# MCU.net
KiCad netlist of a schematic drawn in Altium Designer
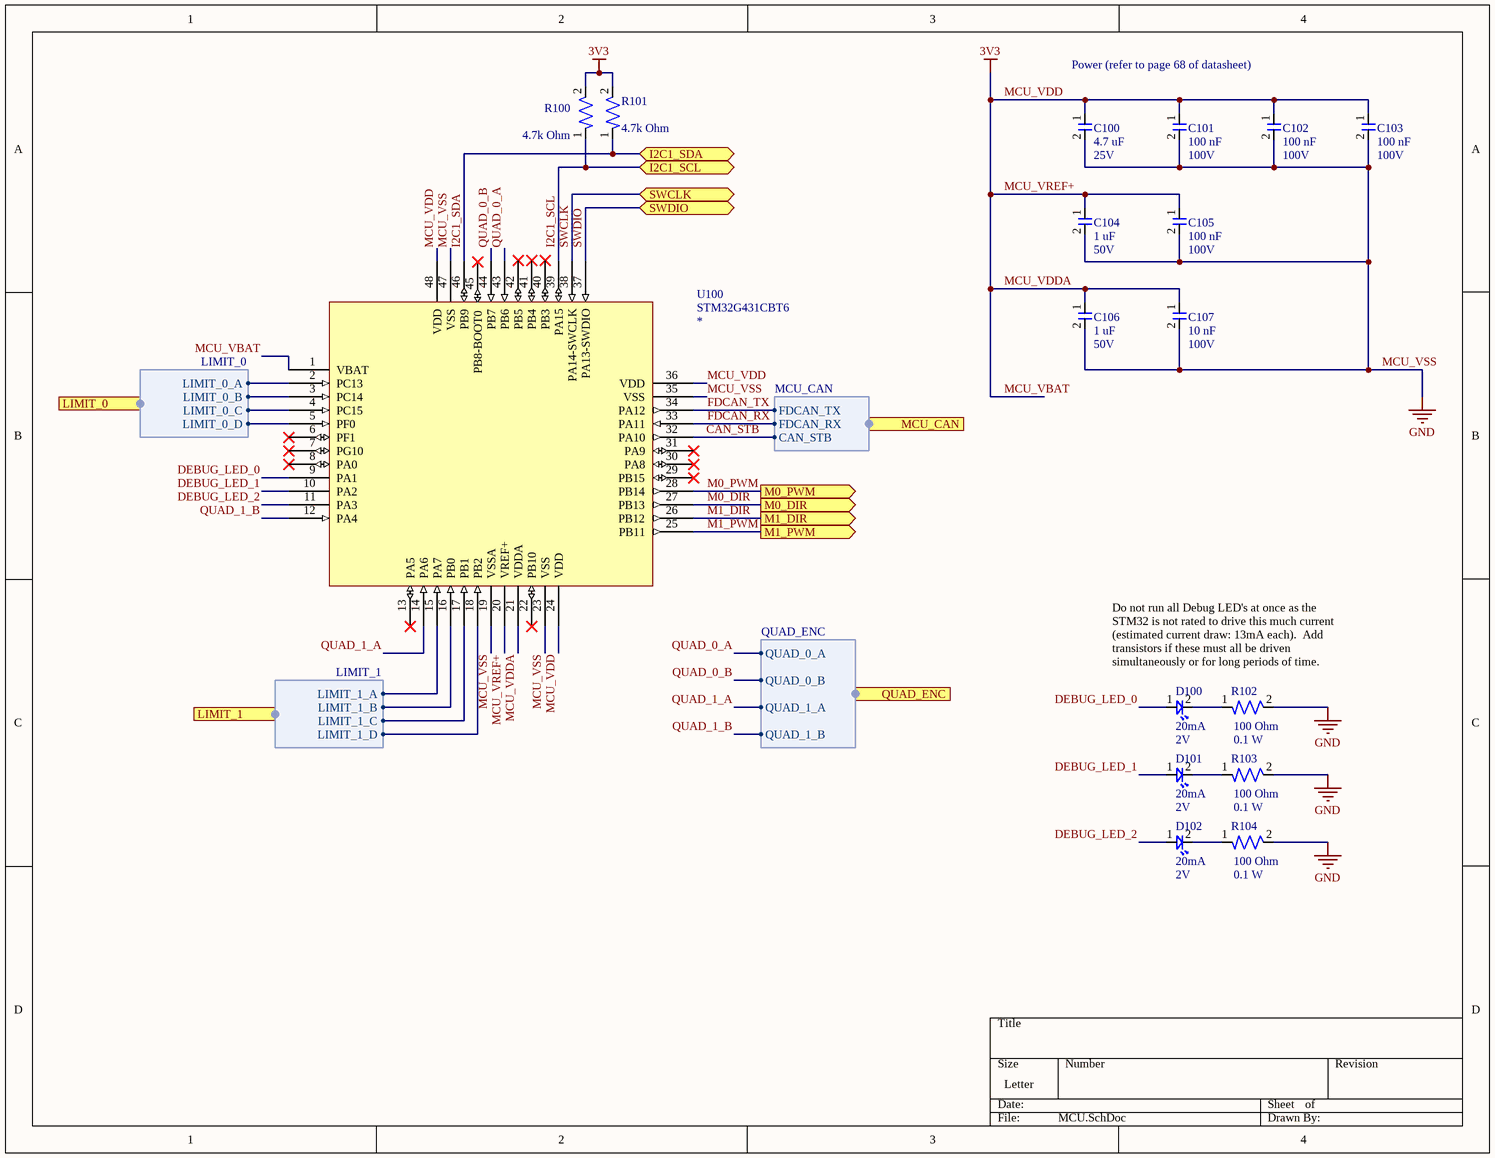
[diagram p0: MCU.SchDoc]

(export (version "E")
  (design (tool "Eeschema 10.0.6"))
  (components
    (comp (ref "C100")
      (value "TMK107BBJ475KA-T")
      (footprint "MasterLib:CAP-0603")
      (description "4.7 µF ±10% 25V Ceramic Capacitor X5R 0603 (1608 Metric)")
      (fields
        (field (name "MANUFACTURER") "Taiyo Yuden")
        (field (name "CAPACITANCE") "4.7 uF")
        (field (name "VOLTAGE RATING") "25V")
        (field (name "TOLERANCE") "10%")
      )
      (libsource (lib "MasterLib") (part "CAP-4.7U-0001"))
    )
    (comp (ref "C101")
      (value "CC0603KRX7R0BB104")
      (footprint "MasterLib:CAP-0603")
      (description "CAP CER 0.1UF 100V X7R 0603")
      (fields
        (field (name "MANUFACTURER") "YAGEO")
        (field (name "CAPACITANCE") "100 nF")
        (field (name "VOLTAGE RATING") "100V")
        (field (name "TOLERANCE") "10%")
      )
      (libsource (lib "MasterLib") (part "CAP-100N-0001"))
    )
    (comp (ref "C102")
      (value "CC0603KRX7R0BB104")
      (footprint "MasterLib:CAP-0603")
      (description "CAP CER 0.1UF 100V X7R 0603")
      (fields
        (field (name "MANUFACTURER") "YAGEO")
        (field (name "CAPACITANCE") "100 nF")
        (field (name "VOLTAGE RATING") "100V")
        (field (name "TOLERANCE") "10%")
      )
      (libsource (lib "MasterLib") (part "CAP-100N-0001"))
    )
    (comp (ref "C103")
      (value "CC0603KRX7R0BB104")
      (footprint "MasterLib:CAP-0603")
      (description "CAP CER 0.1UF 100V X7R 0603")
      (fields
        (field (name "MANUFACTURER") "YAGEO")
        (field (name "CAPACITANCE") "100 nF")
        (field (name "VOLTAGE RATING") "100V")
        (field (name "TOLERANCE") "10%")
      )
      (libsource (lib "MasterLib") (part "CAP-100N-0001"))
    )
    (comp (ref "C104")
      (value "UMK107AB7105KA-T")
      (footprint "MasterLib:CAP-0603")
      (description "1 µF ±10% 50V Ceramic Capacitor X7R 0603 (1608 Metric)")
      (fields
        (field (name "CAPACITANCE") "1 uF")
        (field (name "VOLTAGE") "50V")
        (field (name "TOLERANCE") "10%")
      )
      (libsource (lib "MasterLib") (part "CAP-1U-0002"))
    )
    (comp (ref "C105")
      (value "CC0603KRX7R0BB104")
      (footprint "MasterLib:CAP-0603")
      (description "CAP CER 0.1UF 100V X7R 0603")
      (fields
        (field (name "MANUFACTURER") "YAGEO")
        (field (name "CAPACITANCE") "100 nF")
        (field (name "VOLTAGE RATING") "100V")
        (field (name "TOLERANCE") "10%")
      )
      (libsource (lib "MasterLib") (part "CAP-100N-0001"))
    )
    (comp (ref "C106")
      (value "UMK107AB7105KA-T")
      (footprint "MasterLib:CAP-0603")
      (description "1 µF ±10% 50V Ceramic Capacitor X7R 0603 (1608 Metric)")
      (fields
        (field (name "CAPACITANCE") "1 uF")
        (field (name "VOLTAGE") "50V")
        (field (name "TOLERANCE") "10%")
      )
      (libsource (lib "MasterLib") (part "CAP-1U-0002"))
    )
    (comp (ref "C107")
      (value "CC0402KRX7R0BB103")
      (footprint "MasterLib:CAP-0402")
      (description "10000 pF ±10% 100V Ceramic Capacitor X7R 0402 (1005 Metric)")
      (fields
        (field (name "MANUFACTURER") "YAGEO")
        (field (name "CAPACITANCE") "10 nF")
        (field (name "VOLTAGE RATING") "100V")
        (field (name "TOLERANCE") "10%")
      )
      (libsource (lib "MasterLib") (part "CAP-10N-0001"))
    )
    (comp (ref "D100")
      (value "150060AS75000")
      (footprint "MasterLib:LED-0603")
      (description "CAP CER 0.1UF 100V X7R 0603")
      (fields
        (field (name "MANUFACTURER") "Wurth Electronik")
        (field (name "CURRENT RATING") "20mA")
        (field (name "VF") "2V")
      )
      (libsource (lib "MasterLib") (part "LED_Amber_0001"))
    )
    (comp (ref "D101")
      (value "150060AS75000")
      (footprint "MasterLib:LED-0603")
      (description "CAP CER 0.1UF 100V X7R 0603")
      (fields
        (field (name "MANUFACTURER") "Wurth Electronik")
        (field (name "CURRENT RATING") "20mA")
        (field (name "VF") "2V")
      )
      (libsource (lib "MasterLib") (part "LED_Amber_0001"))
    )
    (comp (ref "D102")
      (value "150060AS75000")
      (footprint "MasterLib:LED-0603")
      (description "CAP CER 0.1UF 100V X7R 0603")
      (fields
        (field (name "MANUFACTURER") "Wurth Electronik")
        (field (name "CURRENT RATING") "20mA")
        (field (name "VF") "2V")
      )
      (libsource (lib "MasterLib") (part "LED_Amber_0001"))
    )
    (comp (ref "R100")
      (value "AF0603FR-074K7L")
      (footprint "MasterLib:RES-0603")
      (description "RES SMD 4.7K OHM 1% 1/10W 0603")
      (fields
        (field (name "MANUFACTURER") "YAGEO")
        (field (name "RESISTANCE") "4.7k Ohm")
        (field (name "TOLERANCE") "1%")
      )
      (libsource (lib "MasterLib") (part "RES-4.7K-0002"))
    )
    (comp (ref "R101")
      (value "AF0603FR-074K7L")
      (footprint "MasterLib:RES-0603")
      (description "RES SMD 4.7K OHM 1% 1/10W 0603")
      (fields
        (field (name "MANUFACTURER") "YAGEO")
        (field (name "RESISTANCE") "4.7k Ohm")
        (field (name "TOLERANCE") "1%")
      )
      (libsource (lib "MasterLib") (part "RES-4.7K-0002"))
    )
    (comp (ref "R102")
      (value "AC0603FR-10100RL")
      (footprint "MasterLib:RES-0603")
      (description "100 Ohms ±1% 0.1W, 1/10W Chip Resistor 0603 (1608 Metric) Automotive AEC-Q200 Thick Film")
      (fields
        (field (name "MANUFACTURER") "YAGEO")
        (field (name "RESISTANCE") "100 Ohm")
        (field (name "TOLERANCE") "1%")
        (field (name "POWER") "0.1 W")
      )
      (libsource (lib "MasterLib") (part "RES-100-0002"))
    )
    (comp (ref "R103")
      (value "AC0603FR-10100RL")
      (footprint "MasterLib:RES-0603")
      (description "100 Ohms ±1% 0.1W, 1/10W Chip Resistor 0603 (1608 Metric) Automotive AEC-Q200 Thick Film")
      (fields
        (field (name "MANUFACTURER") "YAGEO")
        (field (name "RESISTANCE") "100 Ohm")
        (field (name "TOLERANCE") "1%")
        (field (name "POWER") "0.1 W")
      )
      (libsource (lib "MasterLib") (part "RES-100-0002"))
    )
    (comp (ref "R104")
      (value "AC0603FR-10100RL")
      (footprint "MasterLib:RES-0603")
      (description "100 Ohms ±1% 0.1W, 1/10W Chip Resistor 0603 (1608 Metric) Automotive AEC-Q200 Thick Film")
      (fields
        (field (name "MANUFACTURER") "YAGEO")
        (field (name "RESISTANCE") "100 Ohm")
        (field (name "TOLERANCE") "1%")
        (field (name "POWER") "0.1 W")
      )
      (libsource (lib "MasterLib") (part "RES-100-0002"))
    )
    (comp (ref "U100")
      (value "STM32G431CBT6")
      (footprint "Quad48")
      (fields (field (name "PARAMETER 1") "*"))
      (libsource (lib "MasterLib") (part "IC-STM32G431CBT6"))
    )
  )
  (nets
    (net (code "5") (name "/CAN_STB") (class "Default")
      (node (ref "U100") (pin "32") (pinfunction "PA10_32") (pintype "output"))
    )
    (net (code "6") (name "/DEBUG_LED_0") (class "Default")
      (node (ref "D100") (pin "1") (pinfunction "1_1") (pintype "passive"))
      (node (ref "U100") (pin "9") (pinfunction "PA1_9") (pintype "power_in"))
    )
    (net (code "7") (name "/DEBUG_LED_1") (class "Default")
      (node (ref "D101") (pin "1") (pinfunction "1_1") (pintype "passive"))
      (node (ref "U100") (pin "10") (pinfunction "PA2_10") (pintype "power_in"))
    )
    (net (code "8") (name "/DEBUG_LED_2") (class "Default")
      (node (ref "D102") (pin "1") (pinfunction "1_1") (pintype "passive"))
      (node (ref "U100") (pin "11") (pinfunction "PA3_11") (pintype "power_in"))
    )
    (net (code "9") (name "/FDCAN_RX") (class "Default")
      (node (ref "U100") (pin "33") (pinfunction "PA11_33") (pintype "input"))
    )
    (net (code "10") (name "/FDCAN_TX") (class "Default")
      (node (ref "U100") (pin "34") (pinfunction "PA12_34") (pintype "output"))
    )
    (net (code "11") (name "/I2C1_SCL") (class "Default")
      (node (ref "R100") (pin "1") (pinfunction "1_1") (pintype "passive"))
      (node (ref "U100") (pin "39") (pinfunction "PA15_39") (pintype "bidirectional"))
    )
    (net (code "12") (name "/I2C1_SDA") (class "Default")
      (node (ref "R101") (pin "1") (pinfunction "1_1") (pintype "passive"))
      (node (ref "U100") (pin "46") (pinfunction "PB9_46") (pintype "bidirectional"))
    )
    (net (code "13") (name "/LIMIT_0_A") (class "Default")
      (node (ref "U100") (pin "2") (pinfunction "PC13_2") (pintype "input"))
    )
    (net (code "14") (name "/LIMIT_0_B") (class "Default")
      (node (ref "U100") (pin "3") (pinfunction "PC14_3") (pintype "input"))
    )
    (net (code "15") (name "/LIMIT_0_C") (class "Default")
      (node (ref "U100") (pin "4") (pinfunction "PC15_4") (pintype "input"))
    )
    (net (code "16") (name "/LIMIT_0_D") (class "Default")
      (node (ref "U100") (pin "5") (pinfunction "PF0_5") (pintype "input"))
    )
    (net (code "17") (name "/LIMIT_1_A") (class "Default")
      (node (ref "U100") (pin "15") (pinfunction "PA7_15") (pintype "input"))
    )
    (net (code "18") (name "/LIMIT_1_B") (class "Default")
      (node (ref "U100") (pin "16") (pinfunction "PB0_16") (pintype "input"))
    )
    (net (code "19") (name "/LIMIT_1_C") (class "Default")
      (node (ref "U100") (pin "17") (pinfunction "PB1_17") (pintype "input"))
    )
    (net (code "20") (name "/LIMIT_1_D") (class "Default")
      (node (ref "U100") (pin "18") (pinfunction "PB2_18") (pintype "input"))
    )
    (net (code "21") (name "/M0_DIR") (class "Default")
      (node (ref "U100") (pin "27") (pinfunction "PB13_27") (pintype "output"))
    )
    (net (code "22") (name "/M0_PWM") (class "Default")
      (node (ref "U100") (pin "28") (pinfunction "PB14_28") (pintype "output"))
    )
    (net (code "23") (name "/M1_DIR") (class "Default")
      (node (ref "U100") (pin "26") (pinfunction "PB12_26") (pintype "output"))
    )
    (net (code "24") (name "/M1_PWM") (class "Default")
      (node (ref "U100") (pin "25") (pinfunction "PB11_25") (pintype "output"))
    )
    (net (code "25") (name "/QUAD_0_A") (class "Default")
      (node (ref "U100") (pin "43") (pinfunction "PB6_43") (pintype "input"))
    )
    (net (code "26") (name "/QUAD_0_B") (class "Default")
      (node (ref "U100") (pin "44") (pinfunction "PB7_44") (pintype "input"))
    )
    (net (code "27") (name "/QUAD_1_A") (class "Default")
      (node (ref "U100") (pin "14") (pinfunction "PA6_14") (pintype "input"))
    )
    (net (code "28") (name "/QUAD_1_B") (class "Default")
      (node (ref "U100") (pin "12") (pinfunction "PA4_12") (pintype "input"))
    )
    (net (code "29") (name "/SWCLK") (class "Default")
      (node (ref "U100") (pin "38") (pinfunction "PA14-SWCLK_38") (pintype "input"))
    )
    (net (code "30") (name "/SWDIO") (class "Default")
      (node (ref "U100") (pin "37") (pinfunction "PA13-SWDIO_37") (pintype "input"))
    )
    (net (code "35") (name "3V3") (class "Default")
      (node (ref "C100") (pin "1") (pinfunction "1_1") (pintype "passive"))
      (node (ref "C101") (pin "1") (pinfunction "1_1") (pintype "passive"))
      (node (ref "C102") (pin "1") (pinfunction "1_1") (pintype "passive"))
      (node (ref "C103") (pin "1") (pinfunction "1_1") (pintype "passive"))
      (node (ref "C104") (pin "1") (pinfunction "1_1") (pintype "passive"))
      (node (ref "C105") (pin "1") (pinfunction "1_1") (pintype "passive"))
      (node (ref "C106") (pin "1") (pinfunction "1_1") (pintype "passive"))
      (node (ref "C107") (pin "1") (pinfunction "1_1") (pintype "passive"))
      (node (ref "R100") (pin "2") (pinfunction "2_2") (pintype "passive"))
      (node (ref "R101") (pin "2") (pinfunction "2_2") (pintype "passive"))
      (node (ref "U100") (pin "1") (pinfunction "VBAT_1") (pintype "power_in"))
      (node (ref "U100") (pin "20") (pinfunction "VREF+_20") (pintype "power_in"))
      (node (ref "U100") (pin "21") (pinfunction "VDDA_21") (pintype "power_in"))
      (node (ref "U100") (pin "24") (pinfunction "VDD_24") (pintype "power_in"))
      (node (ref "U100") (pin "36") (pinfunction "VDD_36") (pintype "power_in"))
      (node (ref "U100") (pin "48") (pinfunction "VDD_48") (pintype "power_in"))
    )
    (net (code "36") (name "GND") (class "Default")
      (node (ref "C100") (pin "2") (pinfunction "2_2") (pintype "passive"))
      (node (ref "C101") (pin "2") (pinfunction "2_2") (pintype "passive"))
      (node (ref "C102") (pin "2") (pinfunction "2_2") (pintype "passive"))
      (node (ref "C103") (pin "2") (pinfunction "2_2") (pintype "passive"))
      (node (ref "C104") (pin "2") (pinfunction "2_2") (pintype "passive"))
      (node (ref "C105") (pin "2") (pinfunction "2_2") (pintype "passive"))
      (node (ref "C106") (pin "2") (pinfunction "2_2") (pintype "passive"))
      (node (ref "C107") (pin "2") (pinfunction "2_2") (pintype "passive"))
      (node (ref "R102") (pin "2") (pinfunction "2_2") (pintype "passive"))
      (node (ref "R103") (pin "2") (pinfunction "2_2") (pintype "passive"))
      (node (ref "R104") (pin "2") (pinfunction "2_2") (pintype "passive"))
      (node (ref "U100") (pin "19") (pinfunction "VSSA_19") (pintype "power_in"))
      (node (ref "U100") (pin "23") (pinfunction "VSS_23") (pintype "power_in"))
      (node (ref "U100") (pin "35") (pinfunction "VSS_35") (pintype "power_in"))
      (node (ref "U100") (pin "47") (pinfunction "VSS_47") (pintype "power_in"))
    )
    (net (code "37") (name "Net-(D100-Pad2)") (class "Default")
      (node (ref "D100") (pin "2") (pinfunction "2_2") (pintype "passive"))
      (node (ref "R102") (pin "1") (pinfunction "1_1") (pintype "passive"))
    )
    (net (code "38") (name "Net-(D101-Pad2)") (class "Default")
      (node (ref "D101") (pin "2") (pinfunction "2_2") (pintype "passive"))
      (node (ref "R103") (pin "1") (pinfunction "1_1") (pintype "passive"))
    )
    (net (code "39") (name "Net-(D102-Pad2)") (class "Default")
      (node (ref "D102") (pin "2") (pinfunction "2_2") (pintype "passive"))
      (node (ref "R104") (pin "1") (pinfunction "1_1") (pintype "passive"))
    )
    (net (code "40") (name "unconnected-(U100-PA0-Pad8)") (class "Default")
      (node (ref "U100") (pin "8") (pinfunction "PA0_8") (pintype "bidirectional+no_connect"))
    )
    (net (code "41") (name "unconnected-(U100-PA5-Pad13)") (class "Default")
      (node (ref "U100") (pin "13") (pinfunction "PA5_13") (pintype "bidirectional+no_connect"))
    )
    (net (code "42") (name "unconnected-(U100-PA8-Pad30)") (class "Default")
      (node (ref "U100") (pin "30") (pinfunction "PA8_30") (pintype "bidirectional+no_connect"))
    )
    (net (code "43") (name "unconnected-(U100-PA9-Pad31)") (class "Default")
      (node (ref "U100") (pin "31") (pinfunction "PA9_31") (pintype "bidirectional+no_connect"))
    )
    (net (code "44") (name "unconnected-(U100-PB3-Pad40)") (class "Default")
      (node (ref "U100") (pin "40") (pinfunction "PB3_40") (pintype "bidirectional+no_connect"))
    )
    (net (code "45") (name "unconnected-(U100-PB4-Pad41)") (class "Default")
      (node (ref "U100") (pin "41") (pinfunction "PB4_41") (pintype "bidirectional+no_connect"))
    )
    (net (code "46") (name "unconnected-(U100-PB5-Pad42)") (class "Default")
      (node (ref "U100") (pin "42") (pinfunction "PB5_42") (pintype "bidirectional+no_connect"))
    )
    (net (code "47") (name "unconnected-(U100-PB8-BOOT0-Pad45)") (class "Default")
      (node (ref "U100") (pin "45") (pinfunction "PB8-BOOT0_45") (pintype "bidirectional+no_connect"))
    )
    (net (code "48") (name "unconnected-(U100-PB10-Pad22)") (class "Default")
      (node (ref "U100") (pin "22") (pinfunction "PB10_22") (pintype "bidirectional+no_connect"))
    )
    (net (code "49") (name "unconnected-(U100-PB15-Pad29)") (class "Default")
      (node (ref "U100") (pin "29") (pinfunction "PB15_29") (pintype "bidirectional+no_connect"))
    )
    (net (code "50") (name "unconnected-(U100-PF1-Pad6)") (class "Default")
      (node (ref "U100") (pin "6") (pinfunction "PF1_6") (pintype "bidirectional+no_connect"))
    )
    (net (code "51") (name "unconnected-(U100-PG10-Pad7)") (class "Default")
      (node (ref "U100") (pin "7") (pinfunction "PG10_7") (pintype "bidirectional+no_connect"))
    )
  )
)
